# PSU3V3-300mA.net
KiCad netlist of a schematic drawn in Altium Designer
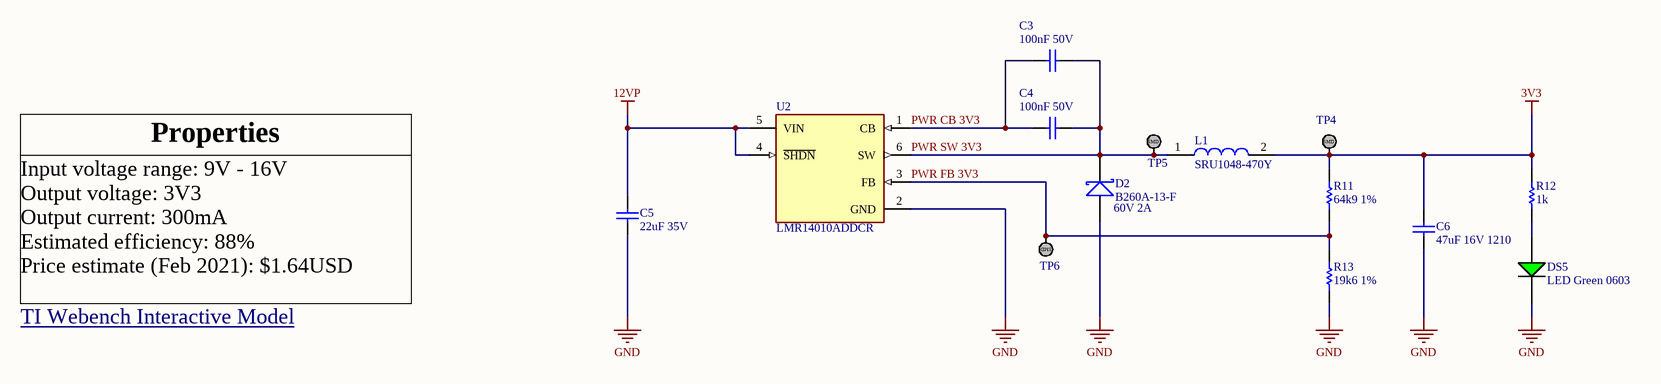
[diagram p0: PSU3V3-300mA.SchDoc]

(export (version "E")
  (design (tool "Eeschema 10.0.6"))
  (components
    (comp (ref "C3")
      (value "100nF 50V")
      (footprint "Cap_Ceramic_0603")
      (description "Capacitor, Ceramic, SMD, 100nF, 50V, 5%, X7R, 0603")
      (libsource (lib "StandardCapacitors") (part "100nF 50V 5% X7R 0603"))
    )
    (comp (ref "C4")
      (value "100nF 50V")
      (footprint "Cap_Ceramic_0603")
      (description "Capacitor, Ceramic, SMD, 100nF, 50V, 5%, X7R, 0603")
      (libsource (lib "StandardCapacitors") (part "100nF 50V 5% X7R 0603"))
    )
    (comp (ref "C5")
      (value "22uF 35V")
      (footprint "Cap_Ceramic_1206")
      (description "22µF ±20% 35V Ceramic Capacitor X5R 1206 (3216 Metric)")
      (libsource (lib "StandardCapacitors") (part "22uF 35V 20% X5R 1206"))
    )
    (comp (ref "C6")
      (value "47uF 16V 1210")
      (footprint "Cap_Ceramic_1210")
      (description "Capacitor, Ceramic, SMD, 47uF, 16V, 5%, X7R, 1210")
      (libsource (lib "StandardCapacitors") (part "47uF 16V 10% X7R 1210"))
    )
    (comp (ref "D2")
      (value "B260A-13-F")
      (footprint "SMA")
      (description "Diode, Schottky Barrier Rectifier, 60 V, 2 A, B260A-13-F")
      (libsource (lib "QUTMS_DiodeLibrary") (part "B260A-13-F"))
    )
    (comp (ref "DS5")
      (value "LED Green 0603")
      (footprint "LED GREEN 0603")
      (libsource (lib "QUTMS_LEDLibrary") (part "LED Green 0603"))
    )
    (comp (ref "L1")
      (value "SRU1048-470Y")
      (footprint "SRU1048")
      (description "Fixed Inductors 47uH 30% SMD 1048")
      (libsource (lib "QUTMS_InductorLibrary") (part "SRU1048-470Y"))
    )
    (comp (ref "R11")
      (value "64k9 1%")
      (footprint "Res_ThinFilm_0603")
      (description "Resistor, SMD, 64k9, 0.1W, 5%, 0603")
      (libsource (lib "StandardResistors") (part "64k9 1% 0603"))
    )
    (comp (ref "R12")
      (value "1k")
      (footprint "Res_ThinFilm_0603")
      (description "Resistor, SMD, 1k, 0.1W, 5%, 0603")
      (libsource (lib "StandardResistors") (part "1k 5% 0603"))
    )
    (comp (ref "R13")
      (value "19k6 1%")
      (footprint "Res_ThinFilm_0603")
      (description "Resistor, SMD, 19k6, 0.1W, 5%, 0603")
      (libsource (lib "StandardResistors") (part "19k6 1% 0603"))
    )
    (comp (ref "TP4")
      (value "TestPoint_SMD")
      (footprint "TestPointSMD")
      (libsource (lib "StandardTest") (part "TestPoint_SMD"))
    )
    (comp (ref "TP5")
      (value "TestPoint_SMD")
      (footprint "TestPointSMD")
      (libsource (lib "StandardTest") (part "TestPoint_SMD"))
    )
    (comp (ref "TP6")
      (value "TestPoint_SMD")
      (footprint "TestPointSMD")
      (libsource (lib "StandardTest") (part "TestPoint_SMD"))
    )
    (comp (ref "U2")
      (value "LMR14010ADDCR")
      (footprint "FP-DDC0006A-MFG")
      (description "IC REG BUCK ADJ 1A TSOT23-6")
      (fields
        (field (name "MANUFACTURER") "Texas Instruments")
        (field (name "OCTOPART") "https://octopart.com/lmr14010addcr-texas+instruments-90753290")
      )
      (libsource (lib "Altium Content Vault") (part "248534993f007311ab4e1890f26e637"))
    )
  )
  (nets
    (net (code "1") (name "/PWR CB 3V3") (class "Default")
      (node (ref "C3") (pin "1") (pinfunction "1_1") (pintype "passive"))
      (node (ref "C4") (pin "1") (pinfunction "1_1") (pintype "passive"))
      (node (ref "U2") (pin "1") (pinfunction "CB_1") (pintype "input"))
    )
    (net (code "2") (name "/PWR FB 3V3") (class "Default")
      (node (ref "R11") (pin "1") (pinfunction "1_1") (pintype "passive"))
      (node (ref "R13") (pin "2") (pinfunction "2_2") (pintype "passive"))
      (node (ref "TP6") (pin "1") (pinfunction "1_1") (pintype "passive"))
      (node (ref "U2") (pin "3") (pinfunction "FB_3") (pintype "input"))
    )
    (net (code "3") (name "/PWR SW 3V3") (class "Default")
      (node (ref "C3") (pin "2") (pinfunction "2_2") (pintype "passive"))
      (node (ref "C4") (pin "2") (pinfunction "2_2") (pintype "passive"))
      (node (ref "D2") (pin "K") (pinfunction "K_K") (pintype "passive"))
      (node (ref "L1") (pin "1") (pinfunction "1_1") (pintype "passive"))
      (node (ref "TP5") (pin "1") (pinfunction "1_1") (pintype "passive"))
      (node (ref "U2") (pin "6") (pinfunction "SW_6") (pintype "output"))
    )
    (net (code "4") (name "3V3") (class "Default")
      (node (ref "C6") (pin "2") (pinfunction "2_2") (pintype "passive"))
      (node (ref "L1") (pin "2") (pinfunction "2_2") (pintype "passive"))
      (node (ref "R11") (pin "2") (pinfunction "2_2") (pintype "passive"))
      (node (ref "R12") (pin "2") (pinfunction "2_2") (pintype "passive"))
      (node (ref "TP4") (pin "1") (pinfunction "1_1") (pintype "passive"))
    )
    (net (code "5") (name "12VP") (class "Default")
      (node (ref "C5") (pin "1") (pinfunction "1_1") (pintype "passive"))
      (node (ref "U2") (pin "4") (pinfunction "~{SHDN}_4") (pintype "input"))
      (node (ref "U2") (pin "5") (pinfunction "VIN_5") (pintype "power_in"))
    )
    (net (code "6") (name "GND") (class "Default")
      (node (ref "C5") (pin "2") (pinfunction "2_2") (pintype "passive"))
      (node (ref "C6") (pin "1") (pinfunction "1_1") (pintype "passive"))
      (node (ref "D2") (pin "A") (pinfunction "A_A") (pintype "passive"))
      (node (ref "DS5") (pin "2") (pinfunction "C_2") (pintype "passive"))
      (node (ref "R13") (pin "1") (pinfunction "1_1") (pintype "passive"))
      (node (ref "U2") (pin "2") (pinfunction "GND_2") (pintype "power_in"))
    )
    (net (code "7") (name "Net-(DS5-A)") (class "Default")
      (node (ref "DS5") (pin "1") (pinfunction "A_1") (pintype "passive"))
      (node (ref "R12") (pin "1") (pinfunction "1_1") (pintype "passive"))
    )
  )
)
